# RHD2132_headstage_accel_mini.net
KiCad netlist of a schematic drawn in EAGLE
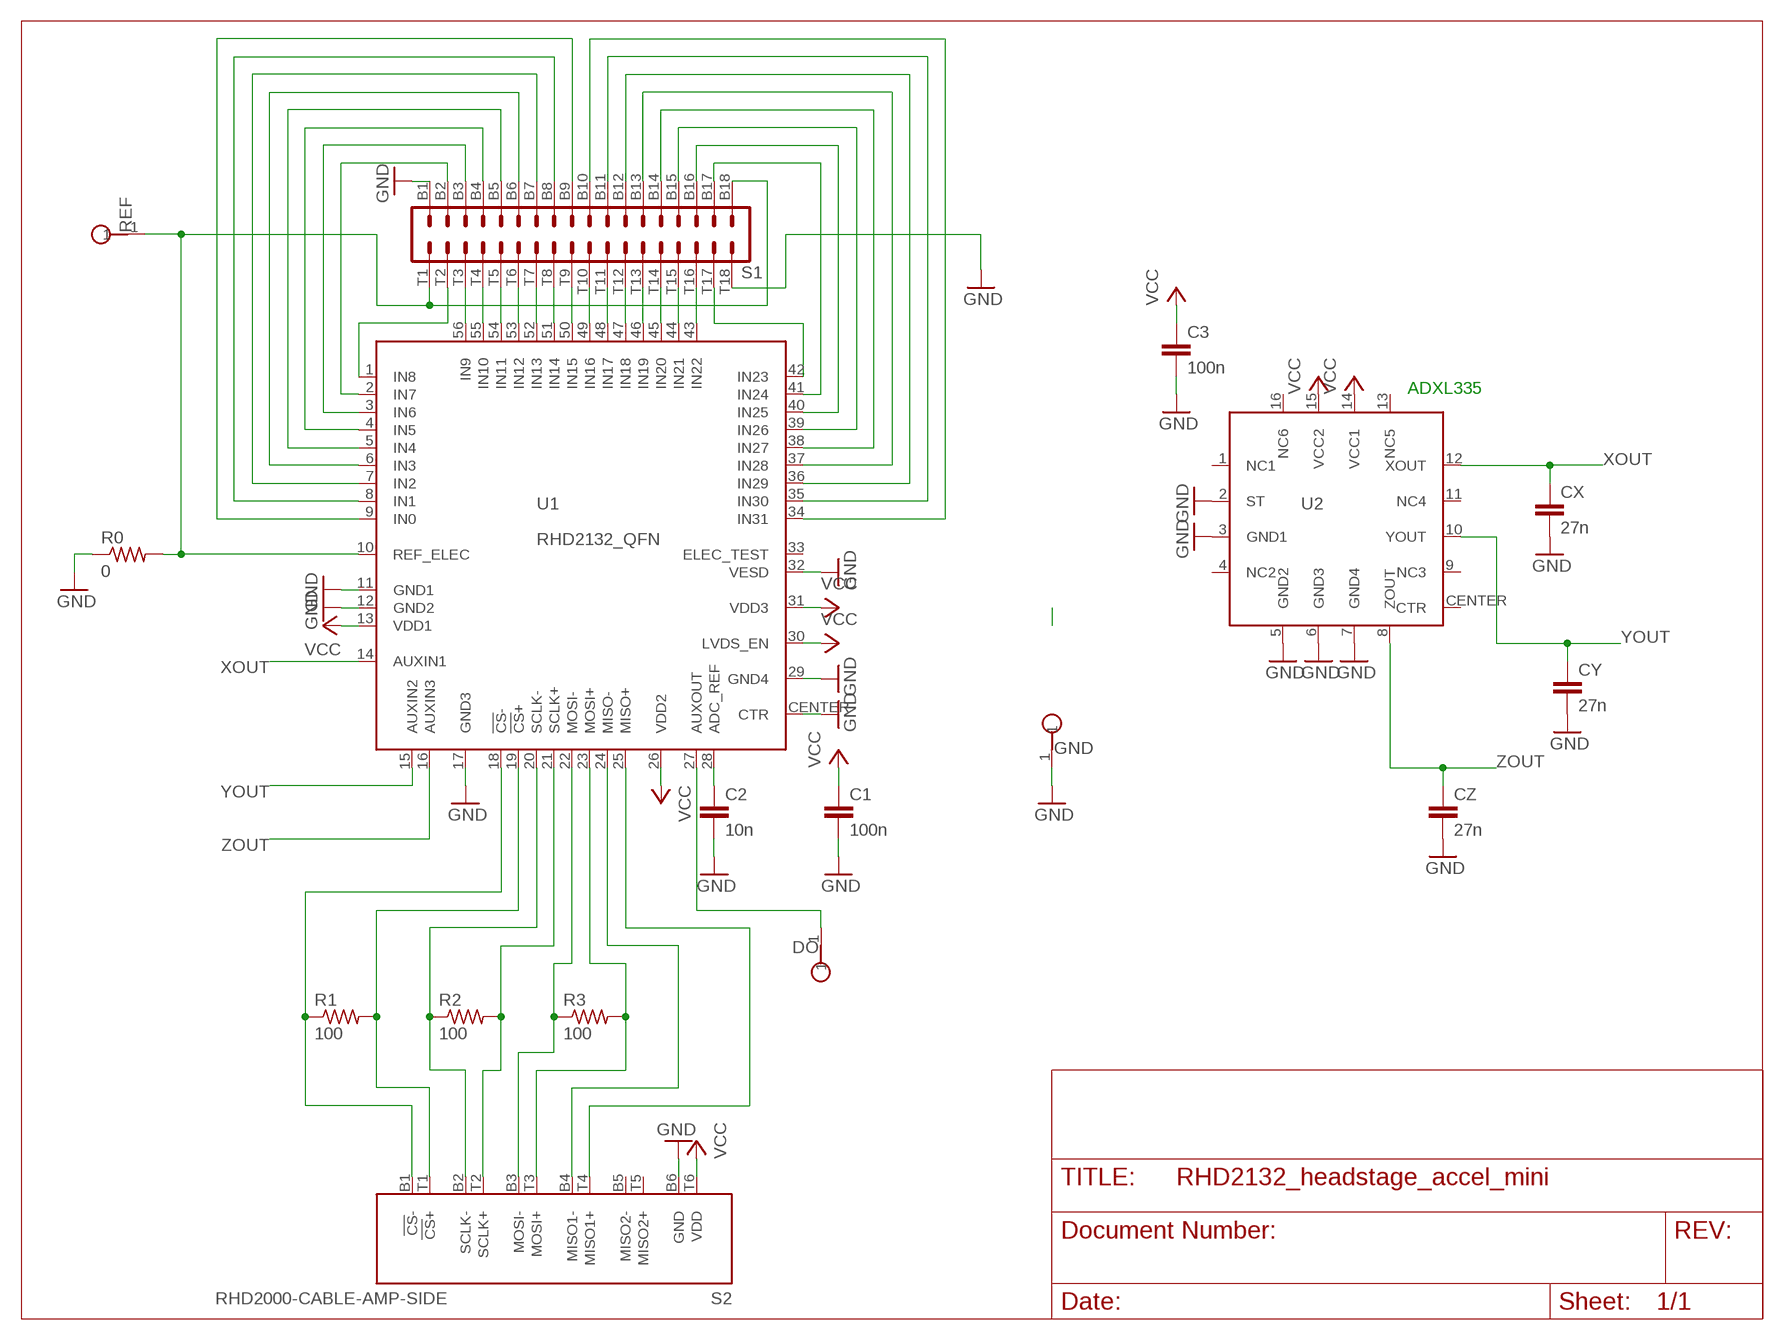
[diagram p0: schematic, sheet 1]

(export (version "E")
  (design (tool "Eeschema 10.0.6"))
  (components
    (comp (ref "C1")
      (value "100n")
      (footprint "eagle-import:0201")
      (libsource (lib "eagle-import") (part "C_0201"))
    )
    (comp (ref "C2")
      (value "10n")
      (footprint "eagle-import:0201")
      (libsource (lib "eagle-import") (part "C_0201"))
    )
    (comp (ref "C3")
      (value "100n")
      (footprint "eagle-import:0201")
      (libsource (lib "eagle-import") (part "C_0201"))
    )
    (comp (ref "CX")
      (value "27n")
      (footprint "eagle-import:0201")
      (libsource (lib "eagle-import") (part "C_0201"))
    )
    (comp (ref "CY")
      (value "27n")
      (footprint "eagle-import:0201")
      (libsource (lib "eagle-import") (part "C_0201"))
    )
    (comp (ref "CZ")
      (value "27n")
      (footprint "eagle-import:0201")
      (libsource (lib "eagle-import") (part "C_0201"))
    )
    (comp (ref "DO")
      (value "TESTPOINT_SMALL")
      (footprint "eagle-import:TESTPOINT_SMALL")
      (libsource (lib "eagle-import") (part "TESTPOINT_SMALL"))
    )
    (comp (ref "GND")
      (value "TESTPOINT_SMALL")
      (footprint "eagle-import:TESTPOINT_SMALL")
      (libsource (lib "eagle-import") (part "TESTPOINT_SMALL"))
    )
    (comp (ref "R0")
      (value "0")
      (footprint "eagle-import:0201")
      (libsource (lib "eagle-import") (part "R_0201"))
    )
    (comp (ref "R1")
      (value "100")
      (footprint "eagle-import:0201")
      (libsource (lib "eagle-import") (part "R_0201"))
    )
    (comp (ref "R2")
      (value "100")
      (footprint "eagle-import:0201")
      (libsource (lib "eagle-import") (part "R_0201"))
    )
    (comp (ref "R3")
      (value "100")
      (footprint "eagle-import:0201")
      (libsource (lib "eagle-import") (part "R_0201"))
    )
    (comp (ref "REF")
      (value "TESTPOINT_SMALL")
      (footprint "eagle-import:TESTPOINT_SMALL")
      (libsource (lib "eagle-import") (part "TESTPOINT_SMALL"))
    )
    (comp (ref "S1")
      (value "OMNETICS_A79025")
      (footprint "eagle-import:OMNETICS_A79025")
      (libsource (lib "eagle-import") (part "OMNETICS_A79025"))
    )
    (comp (ref "S2")
      (value "RHD2000-CABLE-AMP-SIDE")
      (footprint "eagle-import:OMNETICS_PZN-12-AA")
      (libsource (lib "eagle-import") (part "RHD2000-CABLE-AMP-SIDE"))
    )
    (comp (ref "U1")
      (value "RHD2132_QFN")
      (footprint "eagle-import:QFN56_8_X_8_LARGE")
      (libsource (lib "eagle-import") (part "RHD2132_QFN"))
    )
    (comp (ref "U2")
      (value "ADXL335")
      (footprint "eagle-import:ADXL335")
      (libsource (lib "eagle-import") (part "ADXL335"))
    )
  )
  (nets
    (net (code "1") (name "/XOUT") (class "Default")
      (node (ref "CX") (pin "1") (pinfunction "1_1") (pintype "passive"))
      (node (ref "U1") (pin "14") (pinfunction "AUXIN1_14") (pintype "input"))
      (node (ref "U2") (pin "12") (pinfunction "XOUT_12") (pintype "output"))
    )
    (net (code "2") (name "/YOUT") (class "Default")
      (node (ref "CY") (pin "1") (pinfunction "1_1") (pintype "passive"))
      (node (ref "U1") (pin "15") (pinfunction "AUXIN2_15") (pintype "input"))
      (node (ref "U2") (pin "10") (pinfunction "YOUT_10") (pintype "output"))
    )
    (net (code "3") (name "/ZOUT") (class "Default")
      (node (ref "CZ") (pin "1") (pinfunction "1_1") (pintype "passive"))
      (node (ref "U1") (pin "16") (pinfunction "AUXIN3_16") (pintype "input"))
      (node (ref "U2") (pin "8") (pinfunction "ZOUT_8") (pintype "output"))
    )
    (net (code "4") (name "GND") (class "Default")
      (node (ref "C1") (pin "2") (pinfunction "2_2") (pintype "passive"))
      (node (ref "C2") (pin "2") (pinfunction "2_2") (pintype "passive"))
      (node (ref "C3") (pin "2") (pinfunction "2_2") (pintype "passive"))
      (node (ref "CX") (pin "2") (pinfunction "2_2") (pintype "passive"))
      (node (ref "CY") (pin "2") (pinfunction "2_2") (pintype "passive"))
      (node (ref "CZ") (pin "2") (pinfunction "2_2") (pintype "passive"))
      (node (ref "GND") (pin "1") (pinfunction "1_1") (pintype "passive"))
      (node (ref "R0") (pin "1") (pinfunction "1_1") (pintype "passive"))
      (node (ref "S1") (pin "B1") (pinfunction "B1_B1") (pintype "passive"))
      (node (ref "S1") (pin "T18") (pinfunction "T18_T18") (pintype "passive"))
      (node (ref "S2") (pin "B6") (pinfunction "GND_B6") (pintype "power_in"))
      (node (ref "U1") (pin "11") (pinfunction "GND1_11") (pintype "power_in"))
      (node (ref "U1") (pin "12") (pinfunction "GND2_12") (pintype "power_in"))
      (node (ref "U1") (pin "17") (pinfunction "GND3_17") (pintype "power_in"))
      (node (ref "U1") (pin "29") (pinfunction "GND4_29") (pintype "power_in"))
      (node (ref "U1") (pin "32") (pinfunction "VESD_32") (pintype "power_in"))
      (node (ref "U1") (pin "CENTER") (pinfunction "CTR_CENTER") (pintype "power_in"))
      (node (ref "U2") (pin "2") (pinfunction "ST_2") (pintype "input"))
      (node (ref "U2") (pin "3") (pinfunction "GND1_3") (pintype "power_in"))
      (node (ref "U2") (pin "5") (pinfunction "GND2_5") (pintype "power_in"))
      (node (ref "U2") (pin "6") (pinfunction "GND3_6") (pintype "power_in"))
      (node (ref "U2") (pin "7") (pinfunction "GND4_7") (pintype "power_in"))
    )
    (net (code "5") (name "Net-(S2-MISO1+)") (class "Default")
      (node (ref "S2") (pin "T4") (pinfunction "MISO1+_T4") (pintype "bidirectional"))
      (node (ref "U1") (pin "25") (pinfunction "MISO+_25") (pintype "output"))
    )
    (net (code "6") (name "Net-(S2-MISO1-)") (class "Default")
      (node (ref "S2") (pin "B4") (pinfunction "MISO1-_B4") (pintype "bidirectional"))
      (node (ref "U1") (pin "24") (pinfunction "MISO-_24") (pintype "output"))
    )
    (net (code "7") (name "Net-(S2-MOSI+)") (class "Default")
      (node (ref "R3") (pin "2") (pinfunction "2_2") (pintype "passive"))
      (node (ref "S2") (pin "T3") (pinfunction "MOSI+_T3") (pintype "bidirectional"))
      (node (ref "U1") (pin "23") (pinfunction "MOSI+_23") (pintype "input"))
    )
    (net (code "8") (name "Net-(S2-MOSI-)") (class "Default")
      (node (ref "R3") (pin "1") (pinfunction "1_1") (pintype "passive"))
      (node (ref "S2") (pin "B3") (pinfunction "MOSI-_B3") (pintype "bidirectional"))
      (node (ref "U1") (pin "22") (pinfunction "MOSI-_22") (pintype "input"))
    )
    (net (code "9") (name "Net-(S2-SCLK+)") (class "Default")
      (node (ref "R2") (pin "2") (pinfunction "2_2") (pintype "passive"))
      (node (ref "S2") (pin "T2") (pinfunction "SCLK+_T2") (pintype "bidirectional"))
      (node (ref "U1") (pin "21") (pinfunction "SCLK+_21") (pintype "input"))
    )
    (net (code "10") (name "Net-(S2-SCLK-)") (class "Default")
      (node (ref "R2") (pin "1") (pinfunction "1_1") (pintype "passive"))
      (node (ref "S2") (pin "B2") (pinfunction "SCLK-_B2") (pintype "bidirectional"))
      (node (ref "U1") (pin "20") (pinfunction "SCLK-_20") (pintype "input"))
    )
    (net (code "11") (name "Net-(S2-~{CS}+)") (class "Default")
      (node (ref "R1") (pin "2") (pinfunction "2_2") (pintype "passive"))
      (node (ref "S2") (pin "T1") (pinfunction "~{CS}+_T1") (pintype "bidirectional"))
      (node (ref "U1") (pin "19") (pinfunction "~{CS}+_19") (pintype "input"))
    )
    (net (code "12") (name "Net-(S2-~{CS}-)") (class "Default")
      (node (ref "R1") (pin "1") (pinfunction "1_1") (pintype "passive"))
      (node (ref "S2") (pin "B1") (pinfunction "~{CS}-_B1") (pintype "bidirectional"))
      (node (ref "U1") (pin "18") (pinfunction "~{CS}-_18") (pintype "input"))
    )
    (net (code "13") (name "Net-(U1-ADC_REF)") (class "Default")
      (node (ref "C2") (pin "1") (pinfunction "1_1") (pintype "passive"))
      (node (ref "U1") (pin "28") (pinfunction "ADC_REF_28") (pintype "passive"))
    )
    (net (code "14") (name "Net-(U1-AUXOUT)") (class "Default")
      (node (ref "DO") (pin "1") (pinfunction "1_1") (pintype "passive"))
      (node (ref "U1") (pin "27") (pinfunction "AUXOUT_27") (pintype "tri_state"))
    )
    (net (code "15") (name "Net-(U1-IN0)") (class "Default")
      (node (ref "S1") (pin "B9") (pinfunction "B9_B9") (pintype "passive"))
      (node (ref "U1") (pin "9") (pinfunction "IN0_9") (pintype "input"))
    )
    (net (code "16") (name "Net-(U1-IN1)") (class "Default")
      (node (ref "S1") (pin "B8") (pinfunction "B8_B8") (pintype "passive"))
      (node (ref "U1") (pin "8") (pinfunction "IN1_8") (pintype "input"))
    )
    (net (code "17") (name "Net-(U1-IN2)") (class "Default")
      (node (ref "S1") (pin "B7") (pinfunction "B7_B7") (pintype "passive"))
      (node (ref "U1") (pin "7") (pinfunction "IN2_7") (pintype "input"))
    )
    (net (code "18") (name "Net-(U1-IN3)") (class "Default")
      (node (ref "S1") (pin "B6") (pinfunction "B6_B6") (pintype "passive"))
      (node (ref "U1") (pin "6") (pinfunction "IN3_6") (pintype "input"))
    )
    (net (code "19") (name "Net-(U1-IN4)") (class "Default")
      (node (ref "S1") (pin "B5") (pinfunction "B5_B5") (pintype "passive"))
      (node (ref "U1") (pin "5") (pinfunction "IN4_5") (pintype "input"))
    )
    (net (code "20") (name "Net-(U1-IN5)") (class "Default")
      (node (ref "S1") (pin "B4") (pinfunction "B4_B4") (pintype "passive"))
      (node (ref "U1") (pin "4") (pinfunction "IN5_4") (pintype "input"))
    )
    (net (code "21") (name "Net-(U1-IN6)") (class "Default")
      (node (ref "S1") (pin "B3") (pinfunction "B3_B3") (pintype "passive"))
      (node (ref "U1") (pin "3") (pinfunction "IN6_3") (pintype "input"))
    )
    (net (code "22") (name "Net-(U1-IN7)") (class "Default")
      (node (ref "S1") (pin "B2") (pinfunction "B2_B2") (pintype "passive"))
      (node (ref "U1") (pin "2") (pinfunction "IN7_2") (pintype "input"))
    )
    (net (code "23") (name "Net-(U1-IN8)") (class "Default")
      (node (ref "S1") (pin "T2") (pinfunction "T2_T2") (pintype "passive"))
      (node (ref "U1") (pin "1") (pinfunction "IN8_1") (pintype "input"))
    )
    (net (code "24") (name "Net-(U1-IN9)") (class "Default")
      (node (ref "S1") (pin "T3") (pinfunction "T3_T3") (pintype "passive"))
      (node (ref "U1") (pin "56") (pinfunction "IN9_56") (pintype "input"))
    )
    (net (code "25") (name "Net-(U1-IN10)") (class "Default")
      (node (ref "S1") (pin "T4") (pinfunction "T4_T4") (pintype "passive"))
      (node (ref "U1") (pin "55") (pinfunction "IN10_55") (pintype "input"))
    )
    (net (code "26") (name "Net-(U1-IN11)") (class "Default")
      (node (ref "S1") (pin "T5") (pinfunction "T5_T5") (pintype "passive"))
      (node (ref "U1") (pin "54") (pinfunction "IN11_54") (pintype "input"))
    )
    (net (code "27") (name "Net-(U1-IN12)") (class "Default")
      (node (ref "S1") (pin "T6") (pinfunction "T6_T6") (pintype "passive"))
      (node (ref "U1") (pin "53") (pinfunction "IN12_53") (pintype "input"))
    )
    (net (code "28") (name "Net-(U1-IN13)") (class "Default")
      (node (ref "S1") (pin "T7") (pinfunction "T7_T7") (pintype "passive"))
      (node (ref "U1") (pin "52") (pinfunction "IN13_52") (pintype "input"))
    )
    (net (code "29") (name "Net-(U1-IN14)") (class "Default")
      (node (ref "S1") (pin "T8") (pinfunction "T8_T8") (pintype "passive"))
      (node (ref "U1") (pin "51") (pinfunction "IN14_51") (pintype "input"))
    )
    (net (code "30") (name "Net-(U1-IN15)") (class "Default")
      (node (ref "S1") (pin "T9") (pinfunction "T9_T9") (pintype "passive"))
      (node (ref "U1") (pin "50") (pinfunction "IN15_50") (pintype "input"))
    )
    (net (code "31") (name "Net-(U1-IN16)") (class "Default")
      (node (ref "S1") (pin "T10") (pinfunction "T10_T10") (pintype "passive"))
      (node (ref "U1") (pin "49") (pinfunction "IN16_49") (pintype "input"))
    )
    (net (code "32") (name "Net-(U1-IN17)") (class "Default")
      (node (ref "S1") (pin "T11") (pinfunction "T11_T11") (pintype "passive"))
      (node (ref "U1") (pin "48") (pinfunction "IN17_48") (pintype "input"))
    )
    (net (code "33") (name "Net-(U1-IN18)") (class "Default")
      (node (ref "S1") (pin "T12") (pinfunction "T12_T12") (pintype "passive"))
      (node (ref "U1") (pin "47") (pinfunction "IN18_47") (pintype "input"))
    )
    (net (code "34") (name "Net-(U1-IN19)") (class "Default")
      (node (ref "S1") (pin "T13") (pinfunction "T13_T13") (pintype "passive"))
      (node (ref "U1") (pin "46") (pinfunction "IN19_46") (pintype "input"))
    )
    (net (code "35") (name "Net-(U1-IN20)") (class "Default")
      (node (ref "S1") (pin "T14") (pinfunction "T14_T14") (pintype "passive"))
      (node (ref "U1") (pin "45") (pinfunction "IN20_45") (pintype "input"))
    )
    (net (code "36") (name "Net-(U1-IN21)") (class "Default")
      (node (ref "S1") (pin "T15") (pinfunction "T15_T15") (pintype "passive"))
      (node (ref "U1") (pin "44") (pinfunction "IN21_44") (pintype "input"))
    )
    (net (code "37") (name "Net-(U1-IN22)") (class "Default")
      (node (ref "S1") (pin "T16") (pinfunction "T16_T16") (pintype "passive"))
      (node (ref "U1") (pin "43") (pinfunction "IN22_43") (pintype "input"))
    )
    (net (code "38") (name "Net-(U1-IN23)") (class "Default")
      (node (ref "S1") (pin "T17") (pinfunction "T17_T17") (pintype "passive"))
      (node (ref "U1") (pin "42") (pinfunction "IN23_42") (pintype "input"))
    )
    (net (code "39") (name "Net-(U1-IN24)") (class "Default")
      (node (ref "S1") (pin "B17") (pinfunction "B17_B17") (pintype "passive"))
      (node (ref "U1") (pin "41") (pinfunction "IN24_41") (pintype "input"))
    )
    (net (code "40") (name "Net-(U1-IN25)") (class "Default")
      (node (ref "S1") (pin "B16") (pinfunction "B16_B16") (pintype "passive"))
      (node (ref "U1") (pin "40") (pinfunction "IN25_40") (pintype "input"))
    )
    (net (code "41") (name "Net-(U1-IN26)") (class "Default")
      (node (ref "S1") (pin "B15") (pinfunction "B15_B15") (pintype "passive"))
      (node (ref "U1") (pin "39") (pinfunction "IN26_39") (pintype "input"))
    )
    (net (code "42") (name "Net-(U1-IN27)") (class "Default")
      (node (ref "S1") (pin "B14") (pinfunction "B14_B14") (pintype "passive"))
      (node (ref "U1") (pin "38") (pinfunction "IN27_38") (pintype "input"))
    )
    (net (code "43") (name "Net-(U1-IN28)") (class "Default")
      (node (ref "S1") (pin "B13") (pinfunction "B13_B13") (pintype "passive"))
      (node (ref "U1") (pin "37") (pinfunction "IN28_37") (pintype "input"))
    )
    (net (code "44") (name "Net-(U1-IN29)") (class "Default")
      (node (ref "S1") (pin "B12") (pinfunction "B12_B12") (pintype "passive"))
      (node (ref "U1") (pin "36") (pinfunction "IN29_36") (pintype "input"))
    )
    (net (code "45") (name "Net-(U1-IN30)") (class "Default")
      (node (ref "S1") (pin "B11") (pinfunction "B11_B11") (pintype "passive"))
      (node (ref "U1") (pin "35") (pinfunction "IN30_35") (pintype "input"))
    )
    (net (code "46") (name "Net-(U1-IN31)") (class "Default")
      (node (ref "S1") (pin "B10") (pinfunction "B10_B10") (pintype "passive"))
      (node (ref "U1") (pin "34") (pinfunction "IN31_34") (pintype "input"))
    )
    (net (code "47") (name "Net-(U1-REF_ELEC)") (class "Default")
      (node (ref "R0") (pin "2") (pinfunction "2_2") (pintype "passive"))
      (node (ref "REF") (pin "1") (pinfunction "1_1") (pintype "passive"))
      (node (ref "S1") (pin "B18") (pinfunction "B18_B18") (pintype "passive"))
      (node (ref "S1") (pin "T1") (pinfunction "T1_T1") (pintype "passive"))
      (node (ref "U1") (pin "10") (pinfunction "REF_ELEC_10") (pintype "input"))
    )
    (net (code "48") (name "VCC") (class "Default")
      (node (ref "C1") (pin "1") (pinfunction "1_1") (pintype "passive"))
      (node (ref "C3") (pin "1") (pinfunction "1_1") (pintype "passive"))
      (node (ref "S2") (pin "T6") (pinfunction "VDD_T6") (pintype "bidirectional"))
      (node (ref "U1") (pin "13") (pinfunction "VDD1_13") (pintype "power_in"))
      (node (ref "U1") (pin "26") (pinfunction "VDD2_26") (pintype "power_in"))
      (node (ref "U1") (pin "30") (pinfunction "LVDS_EN_30") (pintype "input"))
      (node (ref "U1") (pin "31") (pinfunction "VDD3_31") (pintype "power_in"))
      (node (ref "U2") (pin "14") (pinfunction "VCC1_14") (pintype "power_in"))
      (node (ref "U2") (pin "15") (pinfunction "VCC2_15") (pintype "power_in"))
    )
    (net (code "49") (name "unconnected-(S2-MISO2+-PadT5)") (class "Default")
      (node (ref "S2") (pin "T5") (pinfunction "MISO2+_T5") (pintype "bidirectional"))
    )
    (net (code "50") (name "unconnected-(S2-MISO2--PadB5)") (class "Default")
      (node (ref "S2") (pin "B5") (pinfunction "MISO2-_B5") (pintype "bidirectional"))
    )
    (net (code "51") (name "unconnected-(U1-ELEC_TEST-Pad33)") (class "Default")
      (node (ref "U1") (pin "33") (pinfunction "ELEC_TEST_33") (pintype "input"))
    )
    (net (code "52") (name "unconnected-(U2-CTR-PadCENTER)") (class "Default")
      (node (ref "U2") (pin "CENTER") (pinfunction "CTR_CENTER") (pintype "passive"))
    )
    (net (code "53") (name "unconnected-(U2-NC1-Pad1)") (class "Default")
      (node (ref "U2") (pin "1") (pinfunction "NC1_1") (pintype "no_connect"))
    )
    (net (code "54") (name "unconnected-(U2-NC2-Pad4)") (class "Default")
      (node (ref "U2") (pin "4") (pinfunction "NC2_4") (pintype "no_connect"))
    )
    (net (code "55") (name "unconnected-(U2-NC3-Pad9)") (class "Default")
      (node (ref "U2") (pin "9") (pinfunction "NC3_9") (pintype "no_connect"))
    )
    (net (code "56") (name "unconnected-(U2-NC4-Pad11)") (class "Default")
      (node (ref "U2") (pin "11") (pinfunction "NC4_11") (pintype "no_connect"))
    )
    (net (code "57") (name "unconnected-(U2-NC5-Pad13)") (class "Default")
      (node (ref "U2") (pin "13") (pinfunction "NC5_13") (pintype "no_connect"))
    )
    (net (code "58") (name "unconnected-(U2-NC6-Pad16)") (class "Default")
      (node (ref "U2") (pin "16") (pinfunction "NC6_16") (pintype "no_connect"))
    )
  )
)
